# 11_RK3588_OSC_PLL_PMUIO.net
KiCad netlist of a schematic drawn in Altium Designer
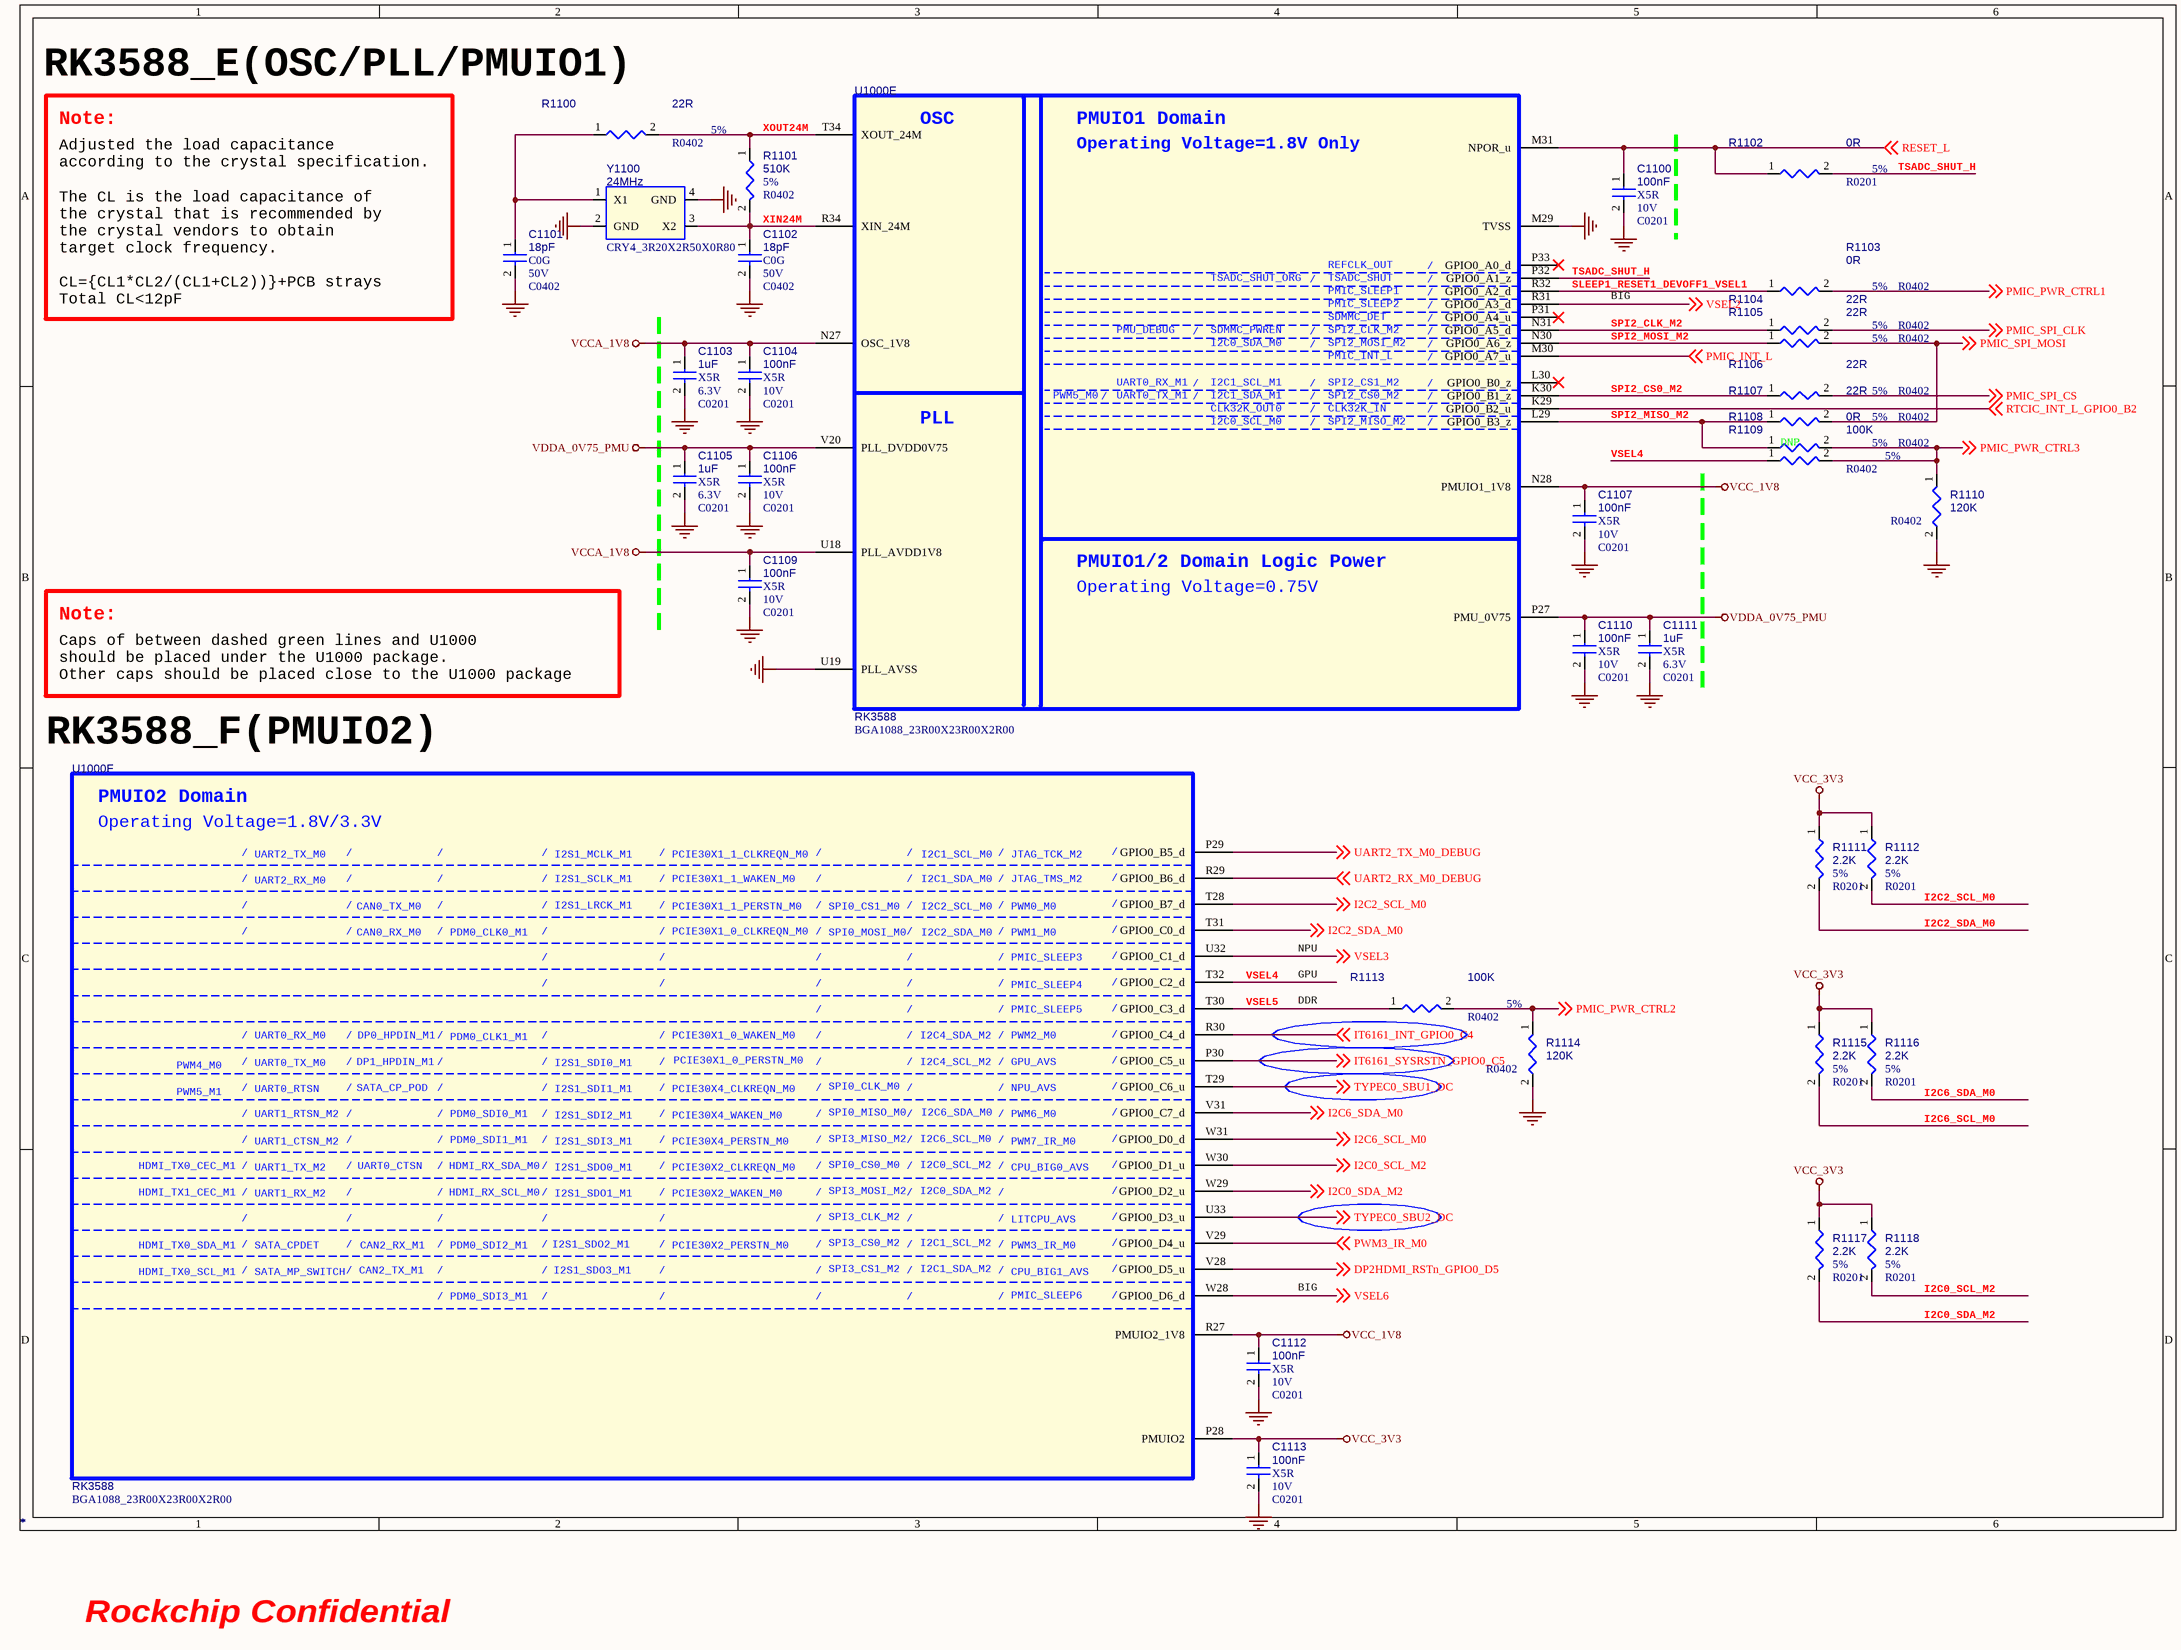
[diagram p0: 11.RK3588_OSC_PLL_PMUIO.SchDoc]

(export (version "E")
  (design (tool "Eeschema 10.0.6"))
  (components
    (comp (ref "C1100")
      (value "*")
      (footprint "C0201")
      (description "cap,100.00nF,+/-10%,10V,X5R,C0201")
      (fields
        (field (name "VOLTAGE") "10V")
        (field (name "PCB FOOTPRINT") "C0201")
        (field (name "DIELECTRIC") "X5R")
        (field (name "MANUFACTURER") "TDK")
        (field (name "TOLERANCE") "10%")
        (field (name "ALTIUM_UNNAMED_1") "100nF")
        (field (name "CREATED BY") "JJJ")
      )
      (libsource (lib "*") (part "CAP NP"))
    )
    (comp (ref "C1101")
      (value "*")
      (footprint "C0402")
      (description "cap,18.00pF,+/-5%,50V,C0G,C0402")
      (fields
        (field (name "VOLTAGE") "50V")
        (field (name "PCB FOOTPRINT") "C0402")
        (field (name "DIELECTRIC") "C0G")
        (field (name "TOLERANCE") "5%")
        (field (name "MANUFACTURER") "TDK")
        (field (name "ALTIUM_UNNAMED_1") "18pF")
        (field (name "CREATED BY") "JJJ")
      )
      (libsource (lib "*") (part "CAP NP"))
    )
    (comp (ref "C1102")
      (value "*")
      (footprint "C0402")
      (description "cap,18.00pF,+/-5%,50V,C0G,C0402")
      (fields
        (field (name "VOLTAGE") "50V")
        (field (name "PCB FOOTPRINT") "C0402")
        (field (name "DIELECTRIC") "C0G")
        (field (name "TOLERANCE") "5%")
        (field (name "MANUFACTURER") "TDK")
        (field (name "ALTIUM_UNNAMED_1") "18pF")
        (field (name "CREATED BY") "JJJ")
      )
      (libsource (lib "*") (part "CAP NP"))
    )
    (comp (ref "C1103")
      (value "*")
      (footprint "C0201")
      (description "cap,1.00uF,+/-20%,6.3V,X5R,C0201")
      (fields
        (field (name "VOLTAGE") "6.3V")
        (field (name "PCB FOOTPRINT") "C0201")
        (field (name "DIELECTRIC") "X5R")
        (field (name "MANUFACTURER") "TDK")
        (field (name "TOLERANCE") "20%")
        (field (name "ALTIUM_UNNAMED_1") "1uF")
        (field (name "CREATED BY") "JJJ")
      )
      (libsource (lib "*") (part "CAP NP"))
    )
    (comp (ref "C1104")
      (value "*")
      (footprint "C0201")
      (description "cap,100.00nF,+/-10%,10V,X5R,C0201")
      (fields
        (field (name "VOLTAGE") "10V")
        (field (name "PCB FOOTPRINT") "C0201")
        (field (name "DIELECTRIC") "X5R")
        (field (name "MANUFACTURER") "TDK")
        (field (name "TOLERANCE") "10%")
        (field (name "ALTIUM_UNNAMED_1") "100nF")
        (field (name "CREATED BY") "JJJ")
      )
      (libsource (lib "*") (part "CAP NP"))
    )
    (comp (ref "C1105")
      (value "*")
      (footprint "C0201")
      (description "cap,1.00uF,+/-20%,6.3V,X5R,C0201")
      (fields
        (field (name "VOLTAGE") "6.3V")
        (field (name "PCB FOOTPRINT") "C0201")
        (field (name "DIELECTRIC") "X5R")
        (field (name "MANUFACTURER") "TDK")
        (field (name "TOLERANCE") "20%")
        (field (name "ALTIUM_UNNAMED_1") "1uF")
        (field (name "CREATED BY") "JJJ")
      )
      (libsource (lib "*") (part "CAP NP"))
    )
    (comp (ref "C1106")
      (value "*")
      (footprint "C0201")
      (description "cap,100.00nF,+/-10%,10V,X5R,C0201")
      (fields
        (field (name "VOLTAGE") "10V")
        (field (name "PCB FOOTPRINT") "C0201")
        (field (name "DIELECTRIC") "X5R")
        (field (name "MANUFACTURER") "TDK")
        (field (name "TOLERANCE") "10%")
        (field (name "ALTIUM_UNNAMED_1") "100nF")
        (field (name "CREATED BY") "JJJ")
      )
      (libsource (lib "*") (part "CAP NP"))
    )
    (comp (ref "C1107")
      (value "*")
      (footprint "C0201")
      (description "cap,100.00nF,+/-10%,10V,X5R,C0201")
      (fields
        (field (name "VOLTAGE") "10V")
        (field (name "PCB FOOTPRINT") "C0201")
        (field (name "DIELECTRIC") "X5R")
        (field (name "TOLERANCE") "10%")
        (field (name "MANUFACTURER") "TDK")
        (field (name "ALTIUM_UNNAMED_1") "100nF")
        (field (name "CREATED BY") "JJJ")
      )
      (libsource (lib "*") (part "CAP NP"))
    )
    (comp (ref "C1109")
      (value "*")
      (footprint "C0201")
      (description "cap,100.00nF,+/-10%,10V,X5R,C0201")
      (fields
        (field (name "VOLTAGE") "10V")
        (field (name "PCB FOOTPRINT") "C0201")
        (field (name "DIELECTRIC") "X5R")
        (field (name "MANUFACTURER") "TDK")
        (field (name "TOLERANCE") "10%")
        (field (name "ALTIUM_UNNAMED_1") "100nF")
        (field (name "CREATED BY") "JJJ")
      )
      (libsource (lib "*") (part "CAP NP"))
    )
    (comp (ref "C1110")
      (value "*")
      (footprint "C0201")
      (description "cap,100.00nF,+/-10%,10V,X5R,C0201")
      (fields
        (field (name "VOLTAGE") "10V")
        (field (name "PCB FOOTPRINT") "C0201")
        (field (name "DIELECTRIC") "X5R")
        (field (name "MANUFACTURER") "TDK")
        (field (name "TOLERANCE") "10%")
        (field (name "ALTIUM_UNNAMED_1") "100nF")
        (field (name "CREATED BY") "JJJ")
      )
      (libsource (lib "*") (part "CAP NP"))
    )
    (comp (ref "C1111")
      (value "*")
      (footprint "C0201")
      (description "cap,1.00uF,+/-20%,6.3V,X5R,C0201")
      (fields
        (field (name "VOLTAGE") "6.3V")
        (field (name "PCB FOOTPRINT") "C0201")
        (field (name "DIELECTRIC") "X5R")
        (field (name "MANUFACTURER") "TDK")
        (field (name "TOLERANCE") "20%")
        (field (name "ALTIUM_UNNAMED_1") "1uF")
        (field (name "CREATED BY") "JJJ")
      )
      (libsource (lib "*") (part "CAP NP"))
    )
    (comp (ref "C1112")
      (value "*")
      (footprint "C0201")
      (description "cap,100.00nF,+/-10%,10V,X5R,C0201")
      (fields
        (field (name "VOLTAGE") "10V")
        (field (name "PCB FOOTPRINT") "C0201")
        (field (name "DIELECTRIC") "X5R")
        (field (name "TOLERANCE") "10%")
        (field (name "MANUFACTURER") "TDK")
        (field (name "ALTIUM_UNNAMED_1") "100nF")
        (field (name "CREATED BY") "JJJ")
      )
      (libsource (lib "*") (part "CAP NP"))
    )
    (comp (ref "C1113")
      (value "*")
      (footprint "C0201")
      (description "cap,100.00nF,+/-10%,10V,X5R,C0201")
      (fields
        (field (name "VOLTAGE") "10V")
        (field (name "PCB FOOTPRINT") "C0201")
        (field (name "DIELECTRIC") "X5R")
        (field (name "TOLERANCE") "10%")
        (field (name "MANUFACTURER") "TDK")
        (field (name "ALTIUM_UNNAMED_1") "100nF")
        (field (name "CREATED BY") "JJJ")
      )
      (libsource (lib "*") (part "CAP NP"))
    )
    (comp (ref "R1100")
      (value "*")
      (footprint "R0402")
      (description "НЁУГєсД¤µзЧи,22R,+/-5%,R0402,1/16W.")
      (fields
        (field (name "PCB FOOTPRINT") "R0402")
        (field (name "TOLERANCE") "5%")
        (field (name "MANUFACTURER") "YAGEO")
        (field (name "ALTIUM_UNNAMED_1") "22R")
        (field (name "CREATED BY") "YTL")
      )
      (libsource (lib "*") (part "RESISTOR_Dup1"))
    )
    (comp (ref "R1101")
      (value "*")
      (footprint "R0402")
      (description "НЁУГєсД¤µзЧи,510K,+/-5%,R0402,1/16W.")
      (fields
        (field (name "PCB FOOTPRINT") "R0402")
        (field (name "TOLERANCE") "5%")
        (field (name "MANUFACTURER") "YAGEO")
        (field (name "ALTIUM_UNNAMED_1") "510K")
        (field (name "CREATED BY") "YTL")
      )
      (libsource (lib "*") (part "RESISTOR_Dup1"))
    )
    (comp (ref "R1102")
      (value "*")
      (footprint "R0402")
      (description "НЁУГєсД¤µзЧи,0R,+/-5%,R0201,1/20W.")
      (fields
        (field (name "PCB FOOTPRINT") "R0201")
        (field (name "TOLERANCE") "5%")
        (field (name "MANUFACTURER") "YAGEO")
        (field (name "ALTIUM_UNNAMED_1") "0R")
        (field (name "CREATED BY") "YTL")
      )
      (libsource (lib "*") (part "RESISTOR_Dup1"))
    )
    (comp (ref "R1103")
      (value "*")
      (footprint "R0402")
      (description "НЁУГєсД¤µзЧи,0R,+/-5%,R0402,1/16W.")
      (fields
        (field (name "PCB FOOTPRINT") "R0402")
        (field (name "TOLERANCE") "5%")
        (field (name "MANUFACTURER") "YAGEO")
        (field (name "ALTIUM_UNNAMED_1") "0R")
        (field (name "CREATED BY") "YTL")
      )
      (libsource (lib "*") (part "RESISTOR_Dup1"))
    )
    (comp (ref "R1104")
      (value "*")
      (footprint "R0402")
      (description "НЁУГєсД¤µзЧи,22R,+/-5%,R0402,1/16W.")
      (fields
        (field (name "PCB FOOTPRINT") "R0402")
        (field (name "TOLERANCE") "5%")
        (field (name "MANUFACTURER") "YAGEO")
        (field (name "ALTIUM_UNNAMED_1") "22R")
        (field (name "CREATED BY") "YTL")
      )
      (libsource (lib "*") (part "RESISTOR_Dup1"))
    )
    (comp (ref "R1105")
      (value "*")
      (footprint "R0402")
      (description "НЁУГєсД¤µзЧи,22R,+/-5%,R0402,1/16W.")
      (fields
        (field (name "PCB FOOTPRINT") "R0402")
        (field (name "TOLERANCE") "5%")
        (field (name "MANUFACTURER") "YAGEO")
        (field (name "ALTIUM_UNNAMED_1") "22R")
        (field (name "CREATED BY") "YTL")
      )
      (libsource (lib "*") (part "RESISTOR_Dup1"))
    )
    (comp (ref "R1106")
      (value "*")
      (footprint "R0402")
      (description "НЁУГєсД¤µзЧи,22R,+/-5%,R0402,1/16W.")
      (fields
        (field (name "PCB FOOTPRINT") "R0402")
        (field (name "TOLERANCE") "5%")
        (field (name "MANUFACTURER") "YAGEO")
        (field (name "ALTIUM_UNNAMED_1") "22R")
        (field (name "CREATED BY") "YTL")
      )
      (libsource (lib "*") (part "RESISTOR_Dup1"))
    )
    (comp (ref "R1107")
      (value "*")
      (footprint "R0402")
      (description "НЁУГєсД¤µзЧи,22R,+/-5%,R0402,1/16W.")
      (fields
        (field (name "PCB FOOTPRINT") "R0402")
        (field (name "TOLERANCE") "5%")
        (field (name "MANUFACTURER") "YAGEO")
        (field (name "ALTIUM_UNNAMED_1") "22R")
        (field (name "CREATED BY") "YTL")
      )
      (libsource (lib "*") (part "RESISTOR_Dup1"))
    )
    (comp (ref "R1108")
      (value "*")
      (footprint "R0402")
      (description "НЁУГєсД¤µзЧи,0R,+/-5%,R0402,1/16W.")
      (fields
        (field (name "PCB FOOTPRINT") "R0402")
        (field (name "TOLERANCE") "5%")
        (field (name "MANUFACTURER") "YAGEO")
        (field (name "OPTION") "DNP")
        (field (name "ALTIUM_UNNAMED_1") "0R")
        (field (name "CREATED BY") "YTL")
      )
      (libsource (lib "*") (part "RESISTOR_Dup1"))
    )
    (comp (ref "R1109")
      (value "*")
      (footprint "R0402")
      (description "НЁУГєсД¤µзЧи,100K,+/-5%,R0402,1/16W.")
      (fields
        (field (name "PCB FOOTPRINT") "R0402")
        (field (name "TOLERANCE") "5%")
        (field (name "MANUFACTURER") "YAGEO")
        (field (name "ALTIUM_UNNAMED_1") "100K")
        (field (name "CREATED BY") "YTL")
      )
      (libsource (lib "*") (part "RESISTOR_Dup1"))
    )
    (comp (ref "R1110")
      (value "*")
      (footprint "R0402")
      (description "НЁУГєсД¤µзЧи,120K,+/-5%,R0402,1/16W.")
      (fields
        (field (name "PCB FOOTPRINT") "R0402")
        (field (name "TOLERANCE") "5%")
        (field (name "MANUFACTURER") "YAGEO")
        (field (name "ALTIUM_UNNAMED_1") "120K")
        (field (name "CREATED BY") "YTL")
      )
      (libsource (lib "*") (part "RESISTOR_Dup1"))
    )
    (comp (ref "R1111")
      (value "*")
      (footprint "R0402")
      (description "НЁУГєсД¤µзЧи,2K2,+/-5%,R0201,1/20W.")
      (fields
        (field (name "PCB FOOTPRINT") "R0201")
        (field (name "TOLERANCE") "5%")
        (field (name "MANUFACTURER") "YAGEO")
        (field (name "ALTIUM_UNNAMED_1") "2.2K")
        (field (name "CREATED BY") "YTL")
      )
      (libsource (lib "*") (part "RESISTOR_Dup1"))
    )
    (comp (ref "R1112")
      (value "*")
      (footprint "R0402")
      (description "НЁУГєсД¤µзЧи,2K2,+/-5%,R0201,1/20W.")
      (fields
        (field (name "PCB FOOTPRINT") "R0201")
        (field (name "TOLERANCE") "5%")
        (field (name "MANUFACTURER") "YAGEO")
        (field (name "ALTIUM_UNNAMED_1") "2.2K")
        (field (name "CREATED BY") "YTL")
      )
      (libsource (lib "*") (part "RESISTOR_Dup1"))
    )
    (comp (ref "R1113")
      (value "*")
      (footprint "R0402")
      (description "НЁУГєсД¤µзЧи,100K,+/-5%,R0402,1/16W.")
      (fields
        (field (name "PCB FOOTPRINT") "R0402")
        (field (name "TOLERANCE") "5%")
        (field (name "MANUFACTURER") "YAGEO")
        (field (name "ALTIUM_UNNAMED_1") "100K")
        (field (name "CREATED BY") "YTL")
      )
      (libsource (lib "*") (part "RESISTOR_Dup1"))
    )
    (comp (ref "R1114")
      (value "*")
      (footprint "R0402")
      (description "НЁУГєсД¤µзЧи,120K,+/-5%,R0402,1/16W.")
      (fields
        (field (name "PCB FOOTPRINT") "R0402")
        (field (name "TOLERANCE") "5%")
        (field (name "MANUFACTURER") "YAGEO")
        (field (name "ALTIUM_UNNAMED_1") "120K")
        (field (name "CREATED BY") "YTL")
      )
      (libsource (lib "*") (part "RESISTOR_Dup1"))
    )
    (comp (ref "R1115")
      (value "*")
      (footprint "R0402")
      (description "НЁУГєсД¤µзЧи,2K2,+/-5%,R0201,1/20W.")
      (fields
        (field (name "PCB FOOTPRINT") "R0201")
        (field (name "TOLERANCE") "5%")
        (field (name "MANUFACTURER") "YAGEO")
        (field (name "ALTIUM_UNNAMED_1") "2.2K")
        (field (name "CREATED BY") "YTL")
      )
      (libsource (lib "*") (part "RESISTOR_Dup1"))
    )
    (comp (ref "R1116")
      (value "*")
      (footprint "R0402")
      (description "НЁУГєсД¤µзЧи,2K2,+/-5%,R0201,1/20W.")
      (fields
        (field (name "PCB FOOTPRINT") "R0201")
        (field (name "TOLERANCE") "5%")
        (field (name "MANUFACTURER") "YAGEO")
        (field (name "ALTIUM_UNNAMED_1") "2.2K")
        (field (name "CREATED BY") "YTL")
      )
      (libsource (lib "*") (part "RESISTOR_Dup1"))
    )
    (comp (ref "R1117")
      (value "*")
      (footprint "R0402")
      (description "НЁУГєсД¤µзЧи,2K2,+/-5%,R0201,1/20W.")
      (fields
        (field (name "PCB FOOTPRINT") "R0201")
        (field (name "TOLERANCE") "5%")
        (field (name "MANUFACTURER") "YAGEO")
        (field (name "ALTIUM_UNNAMED_1") "2.2K")
        (field (name "CREATED BY") "YTL")
      )
      (libsource (lib "*") (part "RESISTOR_Dup1"))
    )
    (comp (ref "R1118")
      (value "*")
      (footprint "R0402")
      (description "НЁУГєсД¤µзЧи,2K2,+/-5%,R0201,1/20W.")
      (fields
        (field (name "PCB FOOTPRINT") "R0201")
        (field (name "TOLERANCE") "5%")
        (field (name "MANUFACTURER") "YAGEO")
        (field (name "ALTIUM_UNNAMED_1") "2.2K")
        (field (name "CREATED BY") "YTL")
      )
      (libsource (lib "*") (part "RESISTOR_Dup1"))
    )
    (comp (ref "U1000")
      (value "*")
      (footprint "BGA1088_23R00X23R00X2R00")
      (description "ROCKCHIP SOC")
      (fields
        (field (name "MANUFACTURER") "Rockchip (ИрРѕОў)")
        (field (name "PCB FOOTPRINT") "BGA1088_23R00X23R00X2R00")
        (field (name "ALTIUM_UNNAMED_1") "RK3588")
        (field (name "CREATED BY") "YWQ")
      )
      (libsource (lib "*") (part "SOC_RK3588"))
    )
    (comp (ref "Y1100")
      (value "*")
      (footprint "CRY-3225")
      (description "ОЮФґѕ§ХсЈ¬24MЈ¬3225,ЎА10ppmЈ¬8pFЈ¬Hosonic")
      (fields
        (field (name "PCB FOOTPRINT") "CRY4_3R20X2R50X0R80")
        (field (name "MANUFACTURER") "Hosonic(єиРЗµзЧУ)")
        (field (name "ALTIUM_UNNAMED_1") "24MHz")
        (field (name "CREATED BY") "JJJ")
      )
      (libsource (lib "*") (part "CRYSTAL_4P"))
    )
  )
  (nets
    (net (code "1") (name "/SLEEP1_RESET1_DEVOFF1_VSEL1") (class "Default")
      (node (ref "R1103") (pin "1") (pinfunction "1_1") (pintype "passive"))
      (node (ref "U1000") (pin "R32") (pinfunction "GPIO0_A2_d_R32") (pintype "passive"))
    )
    (net (code "2") (name "/SPI2_CLK_M2") (class "Default")
      (node (ref "R1104") (pin "1") (pinfunction "1_1") (pintype "passive"))
      (node (ref "U1000") (pin "N31") (pinfunction "GPIO0_A5_d_N31") (pintype "passive"))
    )
    (net (code "3") (name "/SPI2_CS0_M2") (class "Default")
      (node (ref "R1106") (pin "1") (pinfunction "1_1") (pintype "passive"))
      (node (ref "U1000") (pin "K30") (pinfunction "GPIO0_B1_z_K30") (pintype "passive"))
    )
    (net (code "4") (name "/SPI2_MISO_M2") (class "Default")
      (node (ref "R1107") (pin "1") (pinfunction "1_1") (pintype "passive"))
      (node (ref "R1108") (pin "1") (pinfunction "1_1") (pintype "passive"))
      (node (ref "U1000") (pin "L29") (pinfunction "GPIO0_B3_z_L29") (pintype "passive"))
    )
    (net (code "5") (name "/SPI2_MOSI_M2") (class "Default")
      (node (ref "R1105") (pin "1") (pinfunction "1_1") (pintype "passive"))
      (node (ref "U1000") (pin "N30") (pinfunction "GPIO0_A6_z_N30") (pintype "passive"))
    )
    (net (code "6") (name "/TSADC_SHUT_H") (class "Default")
      (node (ref "R1102") (pin "2") (pinfunction "2_2") (pintype "passive"))
      (node (ref "U1000") (pin "P32") (pinfunction "GPIO0_A1_z_P32") (pintype "passive"))
    )
    (net (code "7") (name "/VSEL4") (class "Default")
      (node (ref "R1109") (pin "1") (pinfunction "1_1") (pintype "passive"))
      (node (ref "U1000") (pin "T32") (pinfunction "GPIO0_C2_d_T32") (pintype "passive"))
    )
    (net (code "8") (name "/VSEL5") (class "Default")
      (node (ref "R1113") (pin "1") (pinfunction "1_1") (pintype "passive"))
      (node (ref "U1000") (pin "T30") (pinfunction "GPIO0_C3_d_T30") (pintype "passive"))
    )
    (net (code "9") (name "/XIN24M") (class "Default")
      (node (ref "C1102") (pin "1") (pinfunction "1_1") (pintype "passive"))
      (node (ref "R1101") (pin "2") (pinfunction "2_2") (pintype "passive"))
      (node (ref "U1000") (pin "R34") (pinfunction "XIN_24M_R34") (pintype "passive"))
      (node (ref "Y1100") (pin "3") (pinfunction "X2_3") (pintype "passive"))
    )
    (net (code "10") (name "/XOUT24M") (class "Default")
      (node (ref "R1100") (pin "2") (pinfunction "2_2") (pintype "passive"))
      (node (ref "R1101") (pin "1") (pinfunction "1_1") (pintype "passive"))
      (node (ref "U1000") (pin "T34") (pinfunction "XOUT_24M_T34") (pintype "passive"))
    )
    (net (code "11") (name "DP2HDMI_RSTn_GPIO0_D5") (class "Default")
      (node (ref "U1000") (pin "V28") (pinfunction "GPIO0_D5_u_V28") (pintype "passive"))
    )
    (net (code "12") (name "GND") (class "Default")
      (node (ref "C1100") (pin "2") (pinfunction "2_2") (pintype "passive"))
      (node (ref "C1101") (pin "2") (pinfunction "2_2") (pintype "passive"))
      (node (ref "C1102") (pin "2") (pinfunction "2_2") (pintype "passive"))
      (node (ref "C1103") (pin "2") (pinfunction "2_2") (pintype "passive"))
      (node (ref "C1104") (pin "2") (pinfunction "2_2") (pintype "passive"))
      (node (ref "C1105") (pin "2") (pinfunction "2_2") (pintype "passive"))
      (node (ref "C1106") (pin "2") (pinfunction "2_2") (pintype "passive"))
      (node (ref "C1107") (pin "2") (pinfunction "2_2") (pintype "passive"))
      (node (ref "C1109") (pin "2") (pinfunction "2_2") (pintype "passive"))
      (node (ref "C1110") (pin "2") (pinfunction "2_2") (pintype "passive"))
      (node (ref "C1111") (pin "2") (pinfunction "2_2") (pintype "passive"))
      (node (ref "C1112") (pin "2") (pinfunction "2_2") (pintype "passive"))
      (node (ref "C1113") (pin "2") (pinfunction "2_2") (pintype "passive"))
      (node (ref "R1110") (pin "2") (pinfunction "2_2") (pintype "passive"))
      (node (ref "R1114") (pin "2") (pinfunction "2_2") (pintype "passive"))
      (node (ref "U1000") (pin "M29") (pinfunction "TVSS_M29") (pintype "power_in"))
      (node (ref "U1000") (pin "U19") (pinfunction "PLL_AVSS_U19") (pintype "power_in"))
      (node (ref "Y1100") (pin "2") (pinfunction "GND_2") (pintype "power_in"))
      (node (ref "Y1100") (pin "4") (pinfunction "GND_4") (pintype "power_in"))
    )
    (net (code "13") (name "I2C0_SCL_M2") (class "Default")
      (node (ref "R1118") (pin "2") (pinfunction "2_2") (pintype "passive"))
      (node (ref "U1000") (pin "W30") (pinfunction "GPIO0_D1_u_W30") (pintype "passive"))
    )
    (net (code "14") (name "I2C0_SDA_M2") (class "Default")
      (node (ref "R1117") (pin "2") (pinfunction "2_2") (pintype "passive"))
      (node (ref "U1000") (pin "W29") (pinfunction "GPIO0_D2_u_W29") (pintype "passive"))
    )
    (net (code "15") (name "I2C2_SCL_M0") (class "Default")
      (node (ref "R1112") (pin "2") (pinfunction "2_2") (pintype "passive"))
      (node (ref "U1000") (pin "T28") (pinfunction "GPIO0_B7_d_T28") (pintype "passive"))
    )
    (net (code "16") (name "I2C2_SDA_M0") (class "Default")
      (node (ref "R1111") (pin "2") (pinfunction "2_2") (pintype "passive"))
      (node (ref "U1000") (pin "T31") (pinfunction "GPIO0_C0_d_T31") (pintype "passive"))
    )
    (net (code "17") (name "I2C6_SCL_M0") (class "Default")
      (node (ref "R1115") (pin "2") (pinfunction "2_2") (pintype "passive"))
      (node (ref "U1000") (pin "W31") (pinfunction "GPIO0_D0_d_W31") (pintype "passive"))
    )
    (net (code "18") (name "I2C6_SDA_M0") (class "Default")
      (node (ref "R1116") (pin "2") (pinfunction "2_2") (pintype "passive"))
      (node (ref "U1000") (pin "V31") (pinfunction "GPIO0_C7_d_V31") (pintype "passive"))
    )
    (net (code "19") (name "IT6161_INT_GPIO0_C4") (class "Default")
      (node (ref "U1000") (pin "R30") (pinfunction "GPIO0_C4_d_R30") (pintype "passive"))
    )
    (net (code "20") (name "IT6161_SYSRSTN_GPIO0_C5") (class "Default")
      (node (ref "U1000") (pin "P30") (pinfunction "GPIO0_C5_u_P30") (pintype "passive"))
    )
    (net (code "21") (name "Net-(Y1100-X1)") (class "Default")
      (node (ref "C1101") (pin "1") (pinfunction "1_1") (pintype "passive"))
      (node (ref "R1100") (pin "1") (pinfunction "1_1") (pintype "passive"))
      (node (ref "Y1100") (pin "1") (pinfunction "X1_1") (pintype "passive"))
    )
    (net (code "22") (name "PMIC_INT_L") (class "Default")
      (node (ref "U1000") (pin "M30") (pinfunction "GPIO0_A7_u_M30") (pintype "passive"))
    )
    (net (code "23") (name "PMIC_PWR_CTRL1") (class "Default")
      (node (ref "R1103") (pin "2") (pinfunction "2_2") (pintype "passive"))
    )
    (net (code "24") (name "PMIC_PWR_CTRL2") (class "Default")
      (node (ref "R1113") (pin "2") (pinfunction "2_2") (pintype "passive"))
      (node (ref "R1114") (pin "1") (pinfunction "1_1") (pintype "passive"))
    )
    (net (code "25") (name "PMIC_PWR_CTRL3") (class "Default")
      (node (ref "R1108") (pin "2") (pinfunction "2_2") (pintype "passive"))
      (node (ref "R1109") (pin "2") (pinfunction "2_2") (pintype "passive"))
      (node (ref "R1110") (pin "1") (pinfunction "1_1") (pintype "passive"))
    )
    (net (code "26") (name "PMIC_SPI_CLK") (class "Default")
      (node (ref "R1104") (pin "2") (pinfunction "2_2") (pintype "passive"))
    )
    (net (code "27") (name "PMIC_SPI_CS") (class "Default")
      (node (ref "R1106") (pin "2") (pinfunction "2_2") (pintype "passive"))
    )
    (net (code "28") (name "PMIC_SPI_MOSI") (class "Default")
      (node (ref "R1105") (pin "2") (pinfunction "2_2") (pintype "passive"))
      (node (ref "R1107") (pin "2") (pinfunction "2_2") (pintype "passive"))
    )
    (net (code "29") (name "PWM3_IR_M0") (class "Default")
      (node (ref "U1000") (pin "V29") (pinfunction "GPIO0_D4_u_V29") (pintype "passive"))
    )
    (net (code "30") (name "RESET_L") (class "Default")
      (node (ref "C1100") (pin "1") (pinfunction "1_1") (pintype "passive"))
      (node (ref "R1102") (pin "1") (pinfunction "1_1") (pintype "passive"))
      (node (ref "U1000") (pin "M31") (pinfunction "NPOR_u_M31") (pintype "passive"))
    )
    (net (code "31") (name "RTCIC_INT_L_GPIO0_B2") (class "Default")
      (node (ref "U1000") (pin "K29") (pinfunction "GPIO0_B2_u_K29") (pintype "passive"))
    )
    (net (code "32") (name "TYPEC0_SBU1_DC") (class "Default")
      (node (ref "U1000") (pin "T29") (pinfunction "GPIO0_C6_u_T29") (pintype "passive"))
    )
    (net (code "33") (name "TYPEC0_SBU2_DC") (class "Default")
      (node (ref "U1000") (pin "U33") (pinfunction "GPIO0_D3_u_U33") (pintype "passive"))
    )
    (net (code "34") (name "UART2_RX_M0_DEBUG") (class "Default")
      (node (ref "U1000") (pin "R29") (pinfunction "GPIO0_B6_d_R29") (pintype "passive"))
    )
    (net (code "35") (name "UART2_TX_M0_DEBUG") (class "Default")
      (node (ref "U1000") (pin "P29") (pinfunction "GPIO0_B5_d_P29") (pintype "passive"))
    )
    (net (code "36") (name "VCCA_1V8") (class "Default")
      (node (ref "C1103") (pin "1") (pinfunction "1_1") (pintype "passive"))
      (node (ref "C1104") (pin "1") (pinfunction "1_1") (pintype "passive"))
      (node (ref "C1109") (pin "1") (pinfunction "1_1") (pintype "passive"))
      (node (ref "U1000") (pin "N27") (pinfunction "OSC_1V8_N27") (pintype "power_in"))
      (node (ref "U1000") (pin "U18") (pinfunction "PLL_AVDD1V8_U18") (pintype "power_in"))
    )
    (net (code "37") (name "VCC_1V8") (class "Default")
      (node (ref "C1107") (pin "1") (pinfunction "1_1") (pintype "passive"))
      (node (ref "C1112") (pin "1") (pinfunction "1_1") (pintype "passive"))
      (node (ref "U1000") (pin "N28") (pinfunction "PMUIO1_1V8_N28") (pintype "power_in"))
      (node (ref "U1000") (pin "R27") (pinfunction "PMUIO2_1V8_R27") (pintype "power_in"))
    )
    (net (code "38") (name "VCC_3V3") (class "Default")
      (node (ref "C1113") (pin "1") (pinfunction "1_1") (pintype "passive"))
      (node (ref "R1111") (pin "1") (pinfunction "1_1") (pintype "passive"))
      (node (ref "R1112") (pin "1") (pinfunction "1_1") (pintype "passive"))
      (node (ref "R1115") (pin "1") (pinfunction "1_1") (pintype "passive"))
      (node (ref "R1116") (pin "1") (pinfunction "1_1") (pintype "passive"))
      (node (ref "R1117") (pin "1") (pinfunction "1_1") (pintype "passive"))
      (node (ref "R1118") (pin "1") (pinfunction "1_1") (pintype "passive"))
      (node (ref "U1000") (pin "P28") (pinfunction "PMUIO2_P28") (pintype "power_in"))
    )
    (net (code "39") (name "VDDA_0V75_PMU") (class "Default")
      (node (ref "C1105") (pin "1") (pinfunction "1_1") (pintype "passive"))
      (node (ref "C1106") (pin "1") (pinfunction "1_1") (pintype "passive"))
      (node (ref "C1110") (pin "1") (pinfunction "1_1") (pintype "passive"))
      (node (ref "C1111") (pin "1") (pinfunction "1_1") (pintype "passive"))
      (node (ref "U1000") (pin "P27") (pinfunction "PMU_0V75_P27") (pintype "power_in"))
      (node (ref "U1000") (pin "V20") (pinfunction "PLL_DVDD0V75_V20") (pintype "power_in"))
    )
    (net (code "40") (name "VSEL2") (class "Default")
      (node (ref "U1000") (pin "R31") (pinfunction "GPIO0_A3_d_R31") (pintype "passive"))
    )
    (net (code "41") (name "VSEL3") (class "Default")
      (node (ref "U1000") (pin "U32") (pinfunction "GPIO0_C1_d_U32") (pintype "passive"))
    )
    (net (code "42") (name "VSEL6") (class "Default")
      (node (ref "U1000") (pin "W28") (pinfunction "GPIO0_D6_d_W28") (pintype "passive"))
    )
    (net (code "43") (name "unconnected-(U1000E-GPIO0_A0_d-PadP33)") (class "Default")
      (node (ref "U1000") (pin "P33") (pinfunction "GPIO0_A0_d_P33") (pintype "passive+no_connect"))
    )
    (net (code "44") (name "unconnected-(U1000E-GPIO0_A4_u-PadP31)") (class "Default")
      (node (ref "U1000") (pin "P31") (pinfunction "GPIO0_A4_u_P31") (pintype "passive+no_connect"))
    )
    (net (code "45") (name "unconnected-(U1000E-GPIO0_B0_z-PadL30)") (class "Default")
      (node (ref "U1000") (pin "L30") (pinfunction "GPIO0_B0_z_L30") (pintype "passive+no_connect"))
    )
  )
)
